# bluenrg.net
KiCad netlist of a schematic drawn in Altium Designer
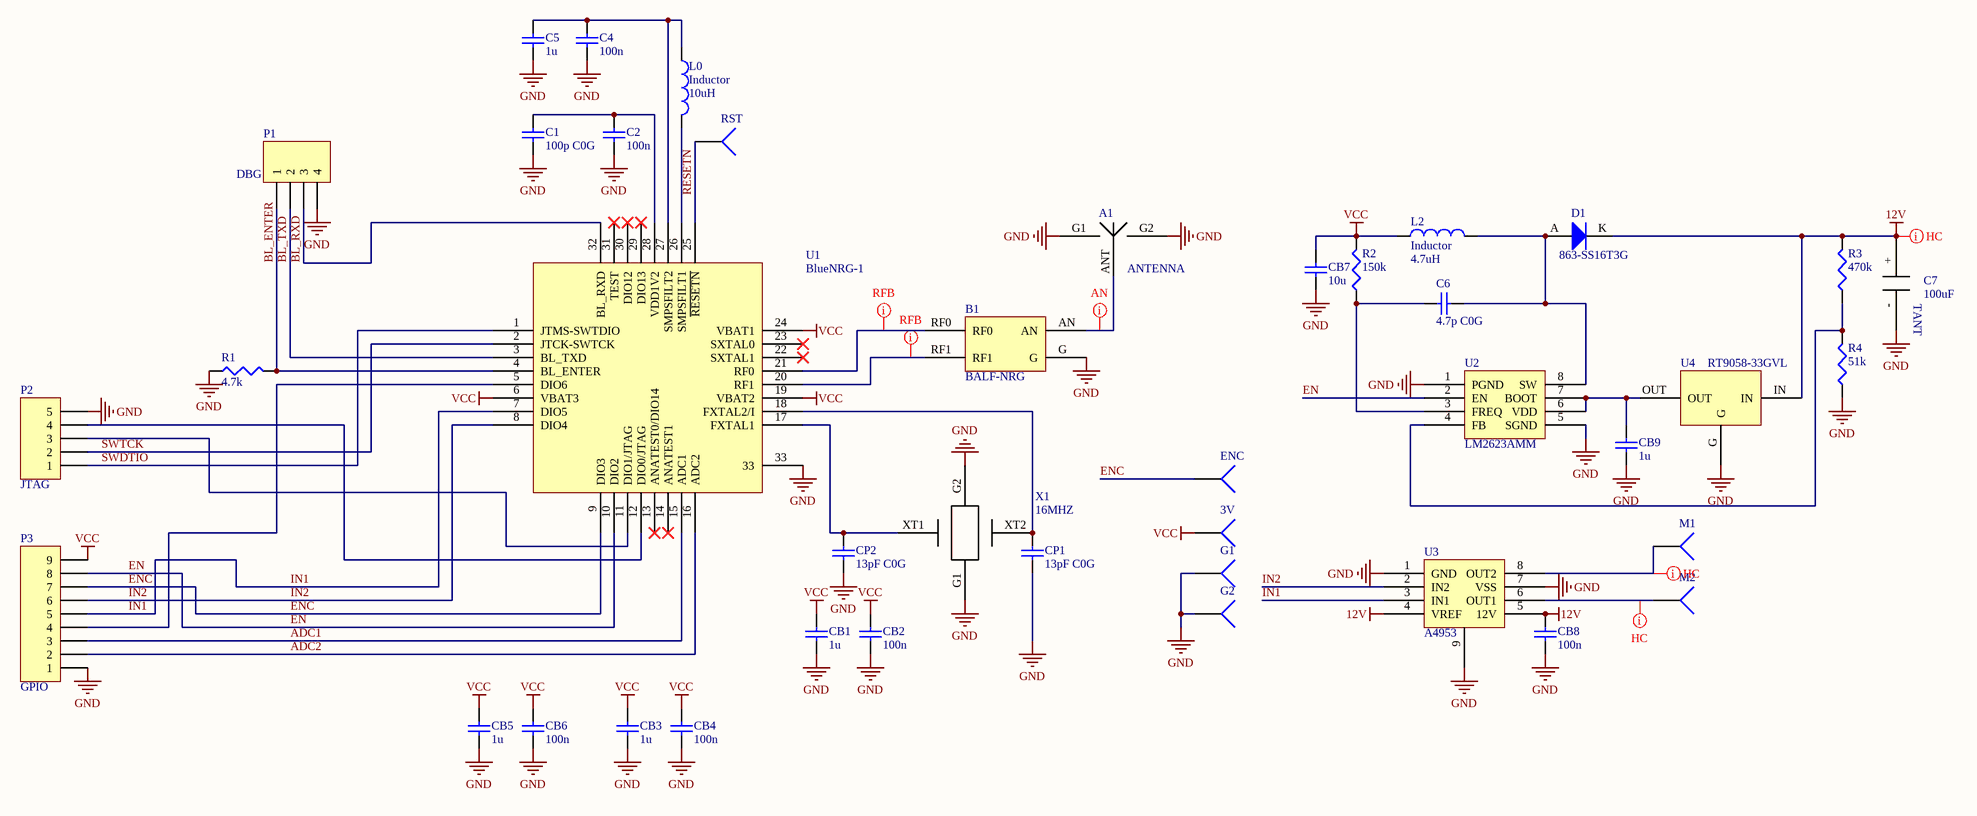
[diagram p0: bluenrg.SchDoc]

(export (version "E")
  (design (tool "Eeschema 10.0.6"))
  (components
    (comp (ref "3V")
      (value "ENC")
      (footprint "MY_PAD")
      (description "Socket")
      (fields (field (name "PUBLISHER") "Altium Limited"))
      (libsource (lib "Miscellaneous Connectors") (part "Socket"))
    )
    (comp (ref "A1") (value "ANTENNA") (footprint "sma") (libsource (lib "components") (part "ANTENNA")))
    (comp (ref "B1")
      (value "BALF-NRG")
      (footprint "BALF-NRG")
      (libsource (lib "components") (part "BALF-NRG"))
    )
    (comp (ref "C1")
      (value "100p C0G")
      (footprint "MY_0603")
      (description "Capacitor (Semiconductor SIM Model)")
      (fields (field (name "PUBLISHER") "Altium Limited"))
      (libsource (lib "Miscellaneous Devices") (part "Cap Semi"))
    )
    (comp (ref "C2")
      (value "100n")
      (footprint "MY_0603")
      (description "Capacitor (Semiconductor SIM Model)")
      (fields (field (name "PUBLISHER") "Altium Limited"))
      (libsource (lib "Miscellaneous Devices") (part "Cap Semi"))
    )
    (comp (ref "C4")
      (value "100n")
      (footprint "MY_0603")
      (description "Capacitor (Semiconductor SIM Model)")
      (fields (field (name "PUBLISHER") "Altium Limited"))
      (libsource (lib "Miscellaneous Devices") (part "Cap Semi"))
    )
    (comp (ref "C5")
      (value "1u")
      (footprint "MY_0603")
      (description "Capacitor (Semiconductor SIM Model)")
      (fields (field (name "PUBLISHER") "Altium Limited"))
      (libsource (lib "Miscellaneous Devices") (part "Cap Semi"))
    )
    (comp (ref "C6")
      (value "4.7p C0G")
      (footprint "MY_0603")
      (description "Capacitor (Semiconductor SIM Model)")
      (fields (field (name "PUBLISHER") "Altium Limited"))
      (libsource (lib "Miscellaneous Devices") (part "Cap Semi"))
    )
    (comp (ref "C7") (value "100uF") (footprint "100uf_tant") (libsource (lib "components") (part "C_TANT")))
    (comp (ref "CB1")
      (value "1u")
      (footprint "MY_0603")
      (description "Capacitor (Semiconductor SIM Model)")
      (fields (field (name "PUBLISHER") "Altium Limited"))
      (libsource (lib "Miscellaneous Devices") (part "Cap Semi"))
    )
    (comp (ref "CB2")
      (value "100n")
      (footprint "MY_0603")
      (description "Capacitor (Semiconductor SIM Model)")
      (fields (field (name "PUBLISHER") "Altium Limited"))
      (libsource (lib "Miscellaneous Devices") (part "Cap Semi"))
    )
    (comp (ref "CB3")
      (value "1u")
      (footprint "MY_0603")
      (description "Capacitor (Semiconductor SIM Model)")
      (fields (field (name "PUBLISHER") "Altium Limited"))
      (libsource (lib "Miscellaneous Devices") (part "Cap Semi"))
    )
    (comp (ref "CB4")
      (value "100n")
      (footprint "MY_0603")
      (description "Capacitor (Semiconductor SIM Model)")
      (fields (field (name "PUBLISHER") "Altium Limited"))
      (libsource (lib "Miscellaneous Devices") (part "Cap Semi"))
    )
    (comp (ref "CB5")
      (value "1u")
      (footprint "MY_0603")
      (description "Capacitor (Semiconductor SIM Model)")
      (fields (field (name "PUBLISHER") "Altium Limited"))
      (libsource (lib "Miscellaneous Devices") (part "Cap Semi"))
    )
    (comp (ref "CB6")
      (value "100n")
      (footprint "MY_0603")
      (description "Capacitor (Semiconductor SIM Model)")
      (fields (field (name "PUBLISHER") "Altium Limited"))
      (libsource (lib "Miscellaneous Devices") (part "Cap Semi"))
    )
    (comp (ref "CB7")
      (value "10u")
      (footprint "MY_0805")
      (description "Capacitor (Semiconductor SIM Model)")
      (fields (field (name "PUBLISHER") "Altium Limited"))
      (libsource (lib "Miscellaneous Devices") (part "Cap Semi"))
    )
    (comp (ref "CB8")
      (value "100n")
      (footprint "MY_0603")
      (description "Capacitor (Semiconductor SIM Model)")
      (fields (field (name "PUBLISHER") "Altium Limited"))
      (libsource (lib "Miscellaneous Devices") (part "Cap Semi"))
    )
    (comp (ref "CB9")
      (value "1u")
      (footprint "MY_0805")
      (description "Capacitor (Semiconductor SIM Model)")
      (fields (field (name "PUBLISHER") "Altium Limited"))
      (libsource (lib "Miscellaneous Devices") (part "Cap Semi"))
    )
    (comp (ref "CP1")
      (value "13pF C0G")
      (footprint "MY_0603")
      (description "Capacitor (Semiconductor SIM Model)")
      (fields (field (name "PUBLISHER") "Altium Limited"))
      (libsource (lib "Miscellaneous Devices") (part "Cap Semi"))
    )
    (comp (ref "CP2")
      (value "13pF C0G")
      (footprint "MY_0603")
      (description "Capacitor (Semiconductor SIM Model)")
      (fields (field (name "PUBLISHER") "Altium Limited"))
      (libsource (lib "Miscellaneous Devices") (part "Cap Semi"))
    )
    (comp (ref "D1")
      (value "863-SS16T3G")
      (footprint "403D")
      (description "Default Diode")
      (fields (field (name "PUBLISHER") "Altium Limited"))
      (libsource (lib "Miscellaneous Devices") (part "Diode"))
    )
    (comp (ref "ENC")
      (value "ENC")
      (footprint "MY_PAD")
      (description "Socket")
      (fields (field (name "PUBLISHER") "Altium Limited"))
      (libsource (lib "Miscellaneous Connectors") (part "Socket"))
    )
    (comp (ref "G1")
      (value "ENC")
      (footprint "MY_PAD")
      (description "Socket")
      (fields (field (name "PUBLISHER") "Altium Limited"))
      (libsource (lib "Miscellaneous Connectors") (part "Socket"))
    )
    (comp (ref "G2")
      (value "ENC")
      (footprint "MY_PAD")
      (description "Socket")
      (fields (field (name "PUBLISHER") "Altium Limited"))
      (libsource (lib "Miscellaneous Connectors") (part "Socket"))
    )
    (comp (ref "L0")
      (value "Inductor")
      (footprint "MY_0805")
      (fields (field (name "ALTIUM_VALUE") "10uH") (field (name "PUBLISHER") "Altium Limited"))
      (libsource (lib "Miscellaneous Devices") (part "Inductor"))
    )
    (comp (ref "L2")
      (value "Inductor")
      (footprint "MY_0805")
      (fields (field (name "ALTIUM_VALUE") "4.7uH") (field (name "PUBLISHER") "Altium Limited"))
      (libsource (lib "Miscellaneous Devices") (part "Inductor"))
    )
    (comp (ref "M1")
      (value "M1")
      (footprint "MPAD")
      (description "Socket")
      (fields (field (name "PUBLISHER") "Altium Limited"))
      (libsource (lib "Miscellaneous Connectors") (part "Socket"))
    )
    (comp (ref "M2")
      (value "M2")
      (footprint "MPAD")
      (description "Socket")
      (fields (field (name "PUBLISHER") "Altium Limited"))
      (libsource (lib "Miscellaneous Connectors") (part "Socket"))
    )
    (comp (ref "P1")
      (value "DBG")
      (footprint "HDR1X4")
      (description "Header, 4-Pin")
      (fields (field (name "PUBLISHER") "Altium Limited"))
      (libsource (lib "Miscellaneous Connectors") (part "Header 4"))
    )
    (comp (ref "P2")
      (value "JTAG")
      (footprint "HDR1X5")
      (description "Header, 5-Pin")
      (fields (field (name "PUBLISHER") "Altium Limited"))
      (libsource (lib "Miscellaneous Connectors") (part "Header 5"))
    )
    (comp (ref "P3")
      (value "GPIO")
      (footprint "HDR1X9")
      (description "Header, 9-Pin")
      (fields (field (name "PUBLISHER") "Altium Limited"))
      (libsource (lib "Miscellaneous Connectors") (part "Header 9"))
    )
    (comp (ref "R1")
      (value "4.7k")
      (footprint "MY_0603")
      (description "Resistor")
      (fields (field (name "PUBLISHER") "Altium Limited"))
      (libsource (lib "Miscellaneous Devices") (part "Res3"))
    )
    (comp (ref "R2")
      (value "150k")
      (footprint "MY_0603")
      (description "Resistor")
      (fields (field (name "PUBLISHER") "Altium Limited"))
      (libsource (lib "Miscellaneous Devices") (part "Res3"))
    )
    (comp (ref "R3")
      (value "470k")
      (footprint "MY_0603")
      (description "Resistor")
      (fields (field (name "PUBLISHER") "Altium Limited"))
      (libsource (lib "Miscellaneous Devices") (part "Res3"))
    )
    (comp (ref "R4")
      (value "51k")
      (footprint "MY_0603")
      (description "Resistor")
      (fields (field (name "PUBLISHER") "Altium Limited"))
      (libsource (lib "Miscellaneous Devices") (part "Res3"))
    )
    (comp (ref "RST")
      (value "M1")
      (footprint "MY_PAD")
      (description "Socket")
      (fields (field (name "PUBLISHER") "Altium Limited"))
      (libsource (lib "Miscellaneous Connectors") (part "Socket"))
    )
    (comp (ref "U1")
      (value "BlueNRG-1")
      (footprint "BlueNRG-1")
      (libsource (lib "components") (part "BlueNRG-1"))
    )
    (comp (ref "U2")
      (value "LM2623AMM")
      (footprint "MSOP-8")
      (libsource (lib "components") (part "LM2623AMM"))
    )
    (comp (ref "U3") (value "A4953") (footprint "MY_SOIC8N_TP") (libsource (lib "components") (part "A4953")))
    (comp (ref "U4")
      (value "RT9058-33GVL")
      (footprint "SOT-23-3L")
      (libsource (lib "components") (part "LDO"))
    )
    (comp (ref "X1")
      (value "16MHZ")
      (footprint "16MHZ_25_20")
      (libsource (lib "components") (part "XTAL_4PIN"))
    )
  )
  (nets
    (net (code "1") (name "/ADC1") (class "Default")
      (node (ref "P3") (pin "3") (pinfunction "3_3") (pintype "passive"))
      (node (ref "U1") (pin "15") (pinfunction "ADC1_15") (pintype "passive"))
    )
    (net (code "2") (name "/ADC2") (class "Default")
      (node (ref "P3") (pin "2") (pinfunction "2_2") (pintype "passive"))
      (node (ref "U1") (pin "16") (pinfunction "ADC2_16") (pintype "passive"))
    )
    (net (code "3") (name "/BL_ENTER") (class "Default")
      (node (ref "P1") (pin "1") (pinfunction "1_1") (pintype "passive"))
      (node (ref "R1") (pin "2") (pinfunction "2_2") (pintype "passive"))
      (node (ref "U1") (pin "4") (pinfunction "BL_ENTER_4") (pintype "passive"))
    )
    (net (code "4") (name "/BL_RXD") (class "Default")
      (node (ref "P1") (pin "3") (pinfunction "3_3") (pintype "passive"))
      (node (ref "U1") (pin "32") (pinfunction "BL_RXD_32") (pintype "passive"))
    )
    (net (code "5") (name "/BL_TXD") (class "Default")
      (node (ref "P1") (pin "2") (pinfunction "2_2") (pintype "passive"))
      (node (ref "U1") (pin "3") (pinfunction "BL_TXD_3") (pintype "passive"))
    )
    (net (code "6") (name "/EN") (class "Default")
      (node (ref "P3") (pin "8") (pinfunction "8_8") (pintype "passive"))
      (node (ref "U1") (pin "10") (pinfunction "DIO2_10") (pintype "passive"))
      (node (ref "U2") (pin "2") (pinfunction "EN_2") (pintype "passive"))
    )
    (net (code "7") (name "/ENC") (class "Default")
      (node (ref "ENC") (pin "1") (pinfunction "1_1") (pintype "passive"))
      (node (ref "P3") (pin "7") (pinfunction "7_7") (pintype "passive"))
      (node (ref "U1") (pin "9") (pinfunction "DIO3_9") (pintype "passive"))
    )
    (net (code "8") (name "/IN1") (class "Default")
      (node (ref "P3") (pin "5") (pinfunction "5_5") (pintype "passive"))
      (node (ref "U1") (pin "7") (pinfunction "DIO5_7") (pintype "passive"))
      (node (ref "U3") (pin "3") (pinfunction "IN1_3") (pintype "passive"))
    )
    (net (code "9") (name "/IN2") (class "Default")
      (node (ref "P3") (pin "6") (pinfunction "6_6") (pintype "passive"))
      (node (ref "U1") (pin "8") (pinfunction "DIO4_8") (pintype "passive"))
      (node (ref "U3") (pin "2") (pinfunction "IN2_2") (pintype "passive"))
    )
    (net (code "10") (name "/RESETN") (class "Default")
      (node (ref "RST") (pin "1") (pinfunction "1_1") (pintype "passive"))
      (node (ref "U1") (pin "25") (pinfunction "~{RESETN}_25") (pintype "passive"))
    )
    (net (code "11") (name "/SWDTIO") (class "Default")
      (node (ref "P2") (pin "1") (pinfunction "1_1") (pintype "passive"))
      (node (ref "U1") (pin "1") (pinfunction "JTMS-SWTDIO_1") (pintype "passive"))
    )
    (net (code "12") (name "/SWTCK") (class "Default")
      (node (ref "P2") (pin "2") (pinfunction "2_2") (pintype "passive"))
      (node (ref "U1") (pin "2") (pinfunction "JTCK-SWTCK_2") (pintype "passive"))
    )
    (net (code "13") (name "12V") (class "Default")
      (node (ref "C7") (pin "+") (pinfunction "+_+") (pintype "passive"))
      (node (ref "CB8") (pin "2") (pinfunction "2_2") (pintype "passive"))
      (node (ref "D1") (pin "K") (pinfunction "K_K") (pintype "passive"))
      (node (ref "R3") (pin "2") (pinfunction "2_2") (pintype "passive"))
      (node (ref "U3") (pin "4") (pinfunction "VREF_4") (pintype "passive"))
      (node (ref "U3") (pin "5") (pinfunction "12V_5") (pintype "passive"))
      (node (ref "U4") (pin "IN") (pinfunction "IN_IN") (pintype "passive"))
    )
    (net (code "14") (name "GND") (class "Default")
      (node (ref "A1") (pin "G1") (pinfunction "G1_G1") (pintype "passive"))
      (node (ref "A1") (pin "G2") (pinfunction "G2_G2") (pintype "passive"))
      (node (ref "B1") (pin "G") (pinfunction "G_G") (pintype "passive"))
      (node (ref "C1") (pin "1") (pinfunction "1_1") (pintype "passive"))
      (node (ref "C2") (pin "1") (pinfunction "1_1") (pintype "passive"))
      (node (ref "C4") (pin "1") (pinfunction "1_1") (pintype "passive"))
      (node (ref "C5") (pin "1") (pinfunction "1_1") (pintype "passive"))
      (node (ref "C7") (pin "-") (pinfunction "-_-") (pintype "passive"))
      (node (ref "CB1") (pin "1") (pinfunction "1_1") (pintype "passive"))
      (node (ref "CB2") (pin "1") (pinfunction "1_1") (pintype "passive"))
      (node (ref "CB3") (pin "1") (pinfunction "1_1") (pintype "passive"))
      (node (ref "CB4") (pin "1") (pinfunction "1_1") (pintype "passive"))
      (node (ref "CB5") (pin "1") (pinfunction "1_1") (pintype "passive"))
      (node (ref "CB6") (pin "1") (pinfunction "1_1") (pintype "passive"))
      (node (ref "CB7") (pin "1") (pinfunction "1_1") (pintype "passive"))
      (node (ref "CB8") (pin "1") (pinfunction "1_1") (pintype "passive"))
      (node (ref "CB9") (pin "1") (pinfunction "1_1") (pintype "passive"))
      (node (ref "CP1") (pin "1") (pinfunction "1_1") (pintype "passive"))
      (node (ref "CP2") (pin "1") (pinfunction "1_1") (pintype "passive"))
      (node (ref "G1") (pin "1") (pinfunction "1_1") (pintype "passive"))
      (node (ref "G2") (pin "1") (pinfunction "1_1") (pintype "passive"))
      (node (ref "P1") (pin "4") (pinfunction "4_4") (pintype "passive"))
      (node (ref "P2") (pin "5") (pinfunction "5_5") (pintype "passive"))
      (node (ref "P3") (pin "1") (pinfunction "1_1") (pintype "passive"))
      (node (ref "R1") (pin "1") (pinfunction "1_1") (pintype "passive"))
      (node (ref "R4") (pin "1") (pinfunction "1_1") (pintype "passive"))
      (node (ref "U1") (pin "33") (pinfunction "33_33") (pintype "passive"))
      (node (ref "U2") (pin "1") (pinfunction "PGND_1") (pintype "passive"))
      (node (ref "U2") (pin "5") (pinfunction "SGND_5") (pintype "passive"))
      (node (ref "U3") (pin "1") (pinfunction "GND_1") (pintype "passive"))
      (node (ref "U3") (pin "7") (pinfunction "VSS_7") (pintype "passive"))
      (node (ref "U3") (pin "9") (pinfunction "G_9") (pintype "passive"))
      (node (ref "U4") (pin "G") (pinfunction "G_G") (pintype "passive"))
      (node (ref "X1") (pin "G1") (pinfunction "G1_G1") (pintype "passive"))
      (node (ref "X1") (pin "G2") (pinfunction "G2_G2") (pintype "passive"))
    )
    (net (code "15") (name "Net-(A1-PadANT)") (class "Default")
      (node (ref "A1") (pin "ANT") (pinfunction "ANT_ANT") (pintype "passive"))
      (node (ref "B1") (pin "AN") (pinfunction "AN_AN") (pintype "passive"))
    )
    (net (code "16") (name "Net-(U1-DIO0{slash}JTAG)") (class "Default")
      (node (ref "P2") (pin "4") (pinfunction "4_4") (pintype "passive"))
      (node (ref "U1") (pin "12") (pinfunction "DIO0/JTAG_12") (pintype "passive"))
    )
    (net (code "17") (name "Net-(U1-DIO1{slash}JTAG)") (class "Default")
      (node (ref "P2") (pin "3") (pinfunction "3_3") (pintype "passive"))
      (node (ref "U1") (pin "11") (pinfunction "DIO1/JTAG_11") (pintype "passive"))
    )
    (net (code "18") (name "Net-(U1-DIO6)") (class "Default")
      (node (ref "P3") (pin "4") (pinfunction "4_4") (pintype "passive"))
      (node (ref "U1") (pin "5") (pinfunction "DIO6_5") (pintype "passive"))
    )
    (net (code "19") (name "Net-(U1-FXTAL1)") (class "Default")
      (node (ref "CP2") (pin "2") (pinfunction "2_2") (pintype "passive"))
      (node (ref "U1") (pin "17") (pinfunction "FXTAL1_17") (pintype "passive"))
      (node (ref "X1") (pin "XT1") (pinfunction "XT1_XT1") (pintype "passive"))
    )
    (net (code "20") (name "Net-(U1-FXTAL2{slash}I)") (class "Default")
      (node (ref "CP1") (pin "2") (pinfunction "2_2") (pintype "passive"))
      (node (ref "U1") (pin "18") (pinfunction "FXTAL2/I_18") (pintype "passive"))
      (node (ref "X1") (pin "XT2") (pinfunction "XT2_XT2") (pintype "passive"))
    )
    (net (code "21") (name "Net-(U1-RF0)") (class "Default")
      (node (ref "B1") (pin "RF0") (pinfunction "RF0_RF0") (pintype "passive"))
      (node (ref "U1") (pin "21") (pinfunction "RF0_21") (pintype "passive"))
    )
    (net (code "22") (name "Net-(U1-RF1)") (class "Default")
      (node (ref "B1") (pin "RF1") (pinfunction "RF1_RF1") (pintype "passive"))
      (node (ref "U1") (pin "20") (pinfunction "RF1_20") (pintype "passive"))
    )
    (net (code "23") (name "Net-(U1-SMPSFILT1)") (class "Default")
      (node (ref "L0") (pin "2") (pinfunction "2_2") (pintype "passive"))
      (node (ref "U1") (pin "26") (pinfunction "SMPSFILT1_26") (pintype "passive"))
    )
    (net (code "24") (name "Net-(U1-SMPSFILT2)") (class "Default")
      (node (ref "C4") (pin "2") (pinfunction "2_2") (pintype "passive"))
      (node (ref "C5") (pin "2") (pinfunction "2_2") (pintype "passive"))
      (node (ref "L0") (pin "1") (pinfunction "1_1") (pintype "passive"))
      (node (ref "U1") (pin "27") (pinfunction "SMPSFILT2_27") (pintype "passive"))
    )
    (net (code "25") (name "Net-(U1-VDD1V2)") (class "Default")
      (node (ref "C1") (pin "2") (pinfunction "2_2") (pintype "passive"))
      (node (ref "C2") (pin "2") (pinfunction "2_2") (pintype "passive"))
      (node (ref "U1") (pin "28") (pinfunction "VDD1V2_28") (pintype "passive"))
    )
    (net (code "26") (name "Net-(U2-BOOT)") (class "Default")
      (node (ref "CB9") (pin "2") (pinfunction "2_2") (pintype "passive"))
      (node (ref "U2") (pin "6") (pinfunction "VDD_6") (pintype "passive"))
      (node (ref "U2") (pin "7") (pinfunction "BOOT_7") (pintype "passive"))
      (node (ref "U4") (pin "OUT") (pinfunction "OUT_OUT") (pintype "passive"))
    )
    (net (code "27") (name "Net-(U2-FB)") (class "Default")
      (node (ref "R3") (pin "1") (pinfunction "1_1") (pintype "passive"))
      (node (ref "R4") (pin "2") (pinfunction "2_2") (pintype "passive"))
      (node (ref "U2") (pin "4") (pinfunction "FB_4") (pintype "passive"))
    )
    (net (code "28") (name "Net-(U2-FREQ)") (class "Default")
      (node (ref "C6") (pin "2") (pinfunction "2_2") (pintype "passive"))
      (node (ref "R2") (pin "1") (pinfunction "1_1") (pintype "passive"))
      (node (ref "U2") (pin "3") (pinfunction "FREQ_3") (pintype "passive"))
    )
    (net (code "29") (name "Net-(U2-SW)") (class "Default")
      (node (ref "C6") (pin "1") (pinfunction "1_1") (pintype "passive"))
      (node (ref "D1") (pin "A") (pinfunction "A_A") (pintype "passive"))
      (node (ref "L2") (pin "2") (pinfunction "2_2") (pintype "passive"))
      (node (ref "U2") (pin "8") (pinfunction "SW_8") (pintype "passive"))
    )
    (net (code "30") (name "Net-(U3-OUT1)") (class "Default")
      (node (ref "M2") (pin "1") (pinfunction "1_1") (pintype "passive"))
      (node (ref "U3") (pin "6") (pinfunction "OUT1_6") (pintype "passive"))
    )
    (net (code "31") (name "Net-(U3-OUT2)") (class "Default")
      (node (ref "M1") (pin "1") (pinfunction "1_1") (pintype "passive"))
      (node (ref "U3") (pin "8") (pinfunction "OUT2_8") (pintype "passive"))
    )
    (net (code "32") (name "VCC") (class "Default")
      (node (ref "3V") (pin "1") (pinfunction "1_1") (pintype "passive"))
      (node (ref "CB1") (pin "2") (pinfunction "2_2") (pintype "passive"))
      (node (ref "CB2") (pin "2") (pinfunction "2_2") (pintype "passive"))
      (node (ref "CB3") (pin "2") (pinfunction "2_2") (pintype "passive"))
      (node (ref "CB4") (pin "2") (pinfunction "2_2") (pintype "passive"))
      (node (ref "CB5") (pin "2") (pinfunction "2_2") (pintype "passive"))
      (node (ref "CB6") (pin "2") (pinfunction "2_2") (pintype "passive"))
      (node (ref "CB7") (pin "2") (pinfunction "2_2") (pintype "passive"))
      (node (ref "L2") (pin "1") (pinfunction "1_1") (pintype "passive"))
      (node (ref "P3") (pin "9") (pinfunction "9_9") (pintype "passive"))
      (node (ref "R2") (pin "2") (pinfunction "2_2") (pintype "passive"))
      (node (ref "U1") (pin "19") (pinfunction "VBAT2_19") (pintype "passive"))
      (node (ref "U1") (pin "24") (pinfunction "VBAT1_24") (pintype "passive"))
      (node (ref "U1") (pin "6") (pinfunction "VBAT3_6") (pintype "passive"))
    )
    (net (code "33") (name "unconnected-(U1-ANATEST0{slash}DIO14-Pad13)") (class "Default")
      (node (ref "U1") (pin "13") (pinfunction "ANATEST0/DIO14_13") (pintype "passive+no_connect"))
    )
    (net (code "34") (name "unconnected-(U1-ANATEST1-Pad14)") (class "Default")
      (node (ref "U1") (pin "14") (pinfunction "ANATEST1_14") (pintype "passive+no_connect"))
    )
    (net (code "35") (name "unconnected-(U1-DIO12-Pad30)") (class "Default")
      (node (ref "U1") (pin "30") (pinfunction "DIO12_30") (pintype "passive+no_connect"))
    )
    (net (code "36") (name "unconnected-(U1-DIO13-Pad29)") (class "Default")
      (node (ref "U1") (pin "29") (pinfunction "DIO13_29") (pintype "passive+no_connect"))
    )
    (net (code "37") (name "unconnected-(U1-SXTAL0-Pad23)") (class "Default")
      (node (ref "U1") (pin "23") (pinfunction "SXTAL0_23") (pintype "passive+no_connect"))
    )
    (net (code "38") (name "unconnected-(U1-SXTAL1-Pad22)") (class "Default")
      (node (ref "U1") (pin "22") (pinfunction "SXTAL1_22") (pintype "passive+no_connect"))
    )
    (net (code "39") (name "unconnected-(U1-TEST-Pad31)") (class "Default")
      (node (ref "U1") (pin "31") (pinfunction "TEST_31") (pintype "passive+no_connect"))
    )
  )
)
